# robot-arm2.net
KiCad netlist of a schematic drawn in Altium Designer
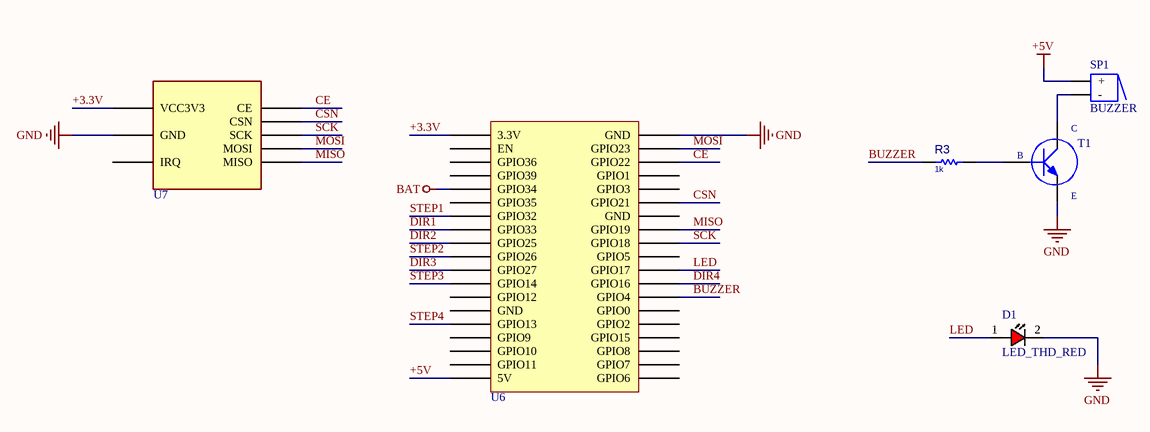
[diagram p0: robot-arm2.SchDoc]

(export (version "E")
  (design (tool "Eeschema 10.0.6"))
  (components
    (comp (ref "D1")
      (value "LED_THD_RED")
      (footprint "LED5MM_RED")
      (description "LED, THD, RED")
      (libsource (lib "Diode_LED") (part "LED_THD_RED"))
    )
    (comp (ref "R3")
      (value "1k")
      (footprint "R025W_AX04")
      (description "RESISTOR, THD")
      (fields (field (name "MANF_P#") "RK73H1ETTP4701F") (field (name "MANF") "KOA SPEER"))
      (libsource (lib "PASSIVE") (part "RES_THD"))
    )
    (comp (ref "SP1")
      (value "BUZZER")
      (footprint "BUZZER 7.62 mm DC")
      (libsource (lib "buzzer") (part "BUZZER"))
    )
    (comp (ref "T1") (value "NPN") (footprint "TO-92") (libsource (lib "transistor") (part "BC547")))
    (comp (ref "U6")
      (value "~")
      (footprint "NODEMCU_ESP32")
      (description "ESP32S")
      (libsource (lib "ArduinoSheild") (part "NODEMCU - ESP32S"))
    )
    (comp (ref "U7")
      (value "NRF24L01_MS")
      (footprint "NRF24L01_H")
      (description "2.4GHz Transceiver MODULE, SMD")
      (libsource (lib "Module") (part "NRF24L01_MS"))
    )
  )
  (nets
    (net (code "1") (name "+5V") (class "Default")
      (node (ref "SP1") (pin "1") (pinfunction "+_1") (pintype "passive"))
      (node (ref "U6") (pin "19") (pinfunction "5V_19") (pintype "passive"))
    )
    (net (code "2") (name "/+3.3V") (class "Default")
      (node (ref "U6") (pin "1") (pinfunction "3.3V_1") (pintype "passive"))
      (node (ref "U7") (pin "2") (pinfunction "VCC3V3_2") (pintype "passive"))
    )
    (net (code "3") (name "/BUZZER") (class "Default")
      (node (ref "R3") (pin "1") (pinfunction "1_1") (pintype "passive"))
      (node (ref "U6") (pin "26") (pinfunction "GPIO4_26") (pintype "passive"))
    )
    (net (code "4") (name "/CE") (class "Default")
      (node (ref "U6") (pin "36") (pinfunction "GPIO22_36") (pintype "passive"))
      (node (ref "U7") (pin "3") (pinfunction "CE_3") (pintype "passive"))
    )
    (net (code "5") (name "/CSN") (class "Default")
      (node (ref "U6") (pin "33") (pinfunction "GPIO21_33") (pintype "passive"))
      (node (ref "U7") (pin "4") (pinfunction "CSN_4") (pintype "passive"))
    )
    (net (code "6") (name "/DIR1") (class "Default")
      (node (ref "U6") (pin "8") (pinfunction "GPIO33_8") (pintype "passive"))
    )
    (net (code "7") (name "/DIR2") (class "Default")
      (node (ref "U6") (pin "9") (pinfunction "GPIO25_9") (pintype "passive"))
    )
    (net (code "8") (name "/DIR3") (class "Default")
      (node (ref "U6") (pin "11") (pinfunction "GPIO27_11") (pintype "passive"))
    )
    (net (code "9") (name "/DIR4") (class "Default")
      (node (ref "U6") (pin "27") (pinfunction "GPIO16_27") (pintype "passive"))
    )
    (net (code "10") (name "/LED") (class "Default")
      (node (ref "D1") (pin "1") (pinfunction "ANODE_1") (pintype "passive"))
      (node (ref "U6") (pin "28") (pinfunction "GPIO17_28") (pintype "passive"))
    )
    (net (code "11") (name "/MISO") (class "Default")
      (node (ref "U6") (pin "31") (pinfunction "GPIO19_31") (pintype "passive"))
      (node (ref "U7") (pin "7") (pinfunction "MISO_7") (pintype "passive"))
    )
    (net (code "12") (name "/MOSI") (class "Default")
      (node (ref "U6") (pin "37") (pinfunction "GPIO23_37") (pintype "passive"))
      (node (ref "U7") (pin "6") (pinfunction "MOSI_6") (pintype "passive"))
    )
    (net (code "13") (name "/SCK") (class "Default")
      (node (ref "U6") (pin "30") (pinfunction "GPIO18_30") (pintype "passive"))
      (node (ref "U7") (pin "5") (pinfunction "SCK_5") (pintype "passive"))
    )
    (net (code "14") (name "/STEP1") (class "Default")
      (node (ref "U6") (pin "7") (pinfunction "GPIO32_7") (pintype "passive"))
    )
    (net (code "15") (name "/STEP2") (class "Default")
      (node (ref "U6") (pin "10") (pinfunction "GPIO26_10") (pintype "passive"))
    )
    (net (code "16") (name "/STEP3") (class "Default")
      (node (ref "U6") (pin "12") (pinfunction "GPIO14_12") (pintype "passive"))
    )
    (net (code "17") (name "/STEP4") (class "Default")
      (node (ref "U6") (pin "15") (pinfunction "GPIO13_15") (pintype "passive"))
    )
    (net (code "18") (name "BAT") (class "Default")
      (node (ref "U6") (pin "5") (pinfunction "GPIO34_5") (pintype "passive"))
    )
    (net (code "19") (name "GND") (class "Default")
      (node (ref "D1") (pin "2") (pinfunction "CATHODE_2") (pintype "passive"))
      (node (ref "T1") (pin "3") (pinfunction "E_3") (pintype "passive"))
      (node (ref "U6") (pin "38") (pinfunction "GND_38") (pintype "passive"))
      (node (ref "U7") (pin "1") (pinfunction "GND_1") (pintype "power_in"))
    )
    (net (code "20") (name "Net-(SP1--)") (class "Default")
      (node (ref "SP1") (pin "2") (pinfunction "-_2") (pintype "passive"))
      (node (ref "T1") (pin "1") (pinfunction "C_1") (pintype "passive"))
    )
    (net (code "21") (name "Net-(T1-B)") (class "Default")
      (node (ref "R3") (pin "2") (pinfunction "2_2") (pintype "passive"))
      (node (ref "T1") (pin "2") (pinfunction "B_2") (pintype "passive"))
    )
    (net (code "22") (name "unconnected-(U6-EN-Pad2)") (class "Default")
      (node (ref "U6") (pin "2") (pinfunction "EN_2") (pintype "passive"))
    )
    (net (code "23") (name "unconnected-(U6-GND-Pad14)") (class "Default")
      (node (ref "U6") (pin "14") (pinfunction "GND_14") (pintype "passive"))
    )
    (net (code "24") (name "unconnected-(U6-GND-Pad32)") (class "Default")
      (node (ref "U6") (pin "32") (pinfunction "GND_32") (pintype "passive"))
    )
    (net (code "25") (name "unconnected-(U6-GPIO0-Pad25)") (class "Default")
      (node (ref "U6") (pin "25") (pinfunction "GPIO0_25") (pintype "passive"))
    )
    (net (code "26") (name "unconnected-(U6-GPIO1-Pad35)") (class "Default")
      (node (ref "U6") (pin "35") (pinfunction "GPIO1_35") (pintype "passive"))
    )
    (net (code "27") (name "unconnected-(U6-GPIO2-Pad24)") (class "Default")
      (node (ref "U6") (pin "24") (pinfunction "GPIO2_24") (pintype "passive"))
    )
    (net (code "28") (name "unconnected-(U6-GPIO3-Pad34)") (class "Default")
      (node (ref "U6") (pin "34") (pinfunction "GPIO3_34") (pintype "passive"))
    )
    (net (code "29") (name "unconnected-(U6-GPIO5-Pad29)") (class "Default")
      (node (ref "U6") (pin "29") (pinfunction "GPIO5_29") (pintype "passive"))
    )
    (net (code "30") (name "unconnected-(U6-GPIO6-Pad20)") (class "Default")
      (node (ref "U6") (pin "20") (pinfunction "GPIO6_20") (pintype "passive"))
    )
    (net (code "31") (name "unconnected-(U6-GPIO7-Pad21)") (class "Default")
      (node (ref "U6") (pin "21") (pinfunction "GPIO7_21") (pintype "passive"))
    )
    (net (code "32") (name "unconnected-(U6-GPIO8-Pad22)") (class "Default")
      (node (ref "U6") (pin "22") (pinfunction "GPIO8_22") (pintype "passive"))
    )
    (net (code "33") (name "unconnected-(U6-GPIO9-Pad16)") (class "Default")
      (node (ref "U6") (pin "16") (pinfunction "GPIO9_16") (pintype "passive"))
    )
    (net (code "34") (name "unconnected-(U6-GPIO10-Pad17)") (class "Default")
      (node (ref "U6") (pin "17") (pinfunction "GPIO10_17") (pintype "passive"))
    )
    (net (code "35") (name "unconnected-(U6-GPIO11-Pad18)") (class "Default")
      (node (ref "U6") (pin "18") (pinfunction "GPIO11_18") (pintype "passive"))
    )
    (net (code "36") (name "unconnected-(U6-GPIO12-Pad13)") (class "Default")
      (node (ref "U6") (pin "13") (pinfunction "GPIO12_13") (pintype "passive"))
    )
    (net (code "37") (name "unconnected-(U6-GPIO15-Pad23)") (class "Default")
      (node (ref "U6") (pin "23") (pinfunction "GPIO15_23") (pintype "passive"))
    )
    (net (code "38") (name "unconnected-(U6-GPIO35-Pad6)") (class "Default")
      (node (ref "U6") (pin "6") (pinfunction "GPIO35_6") (pintype "passive"))
    )
    (net (code "39") (name "unconnected-(U6-GPIO36-Pad3)") (class "Default")
      (node (ref "U6") (pin "3") (pinfunction "GPIO36_3") (pintype "passive"))
    )
    (net (code "40") (name "unconnected-(U6-GPIO39-Pad4)") (class "Default")
      (node (ref "U6") (pin "4") (pinfunction "GPIO39_4") (pintype "passive"))
    )
    (net (code "41") (name "unconnected-(U7-IRQ-Pad8)") (class "Default")
      (node (ref "U7") (pin "8") (pinfunction "IRQ_8") (pintype "passive"))
    )
  )
)
